# Logic_Engine_-_Front_LED.net
KiCad netlist of a schematic drawn in EAGLE
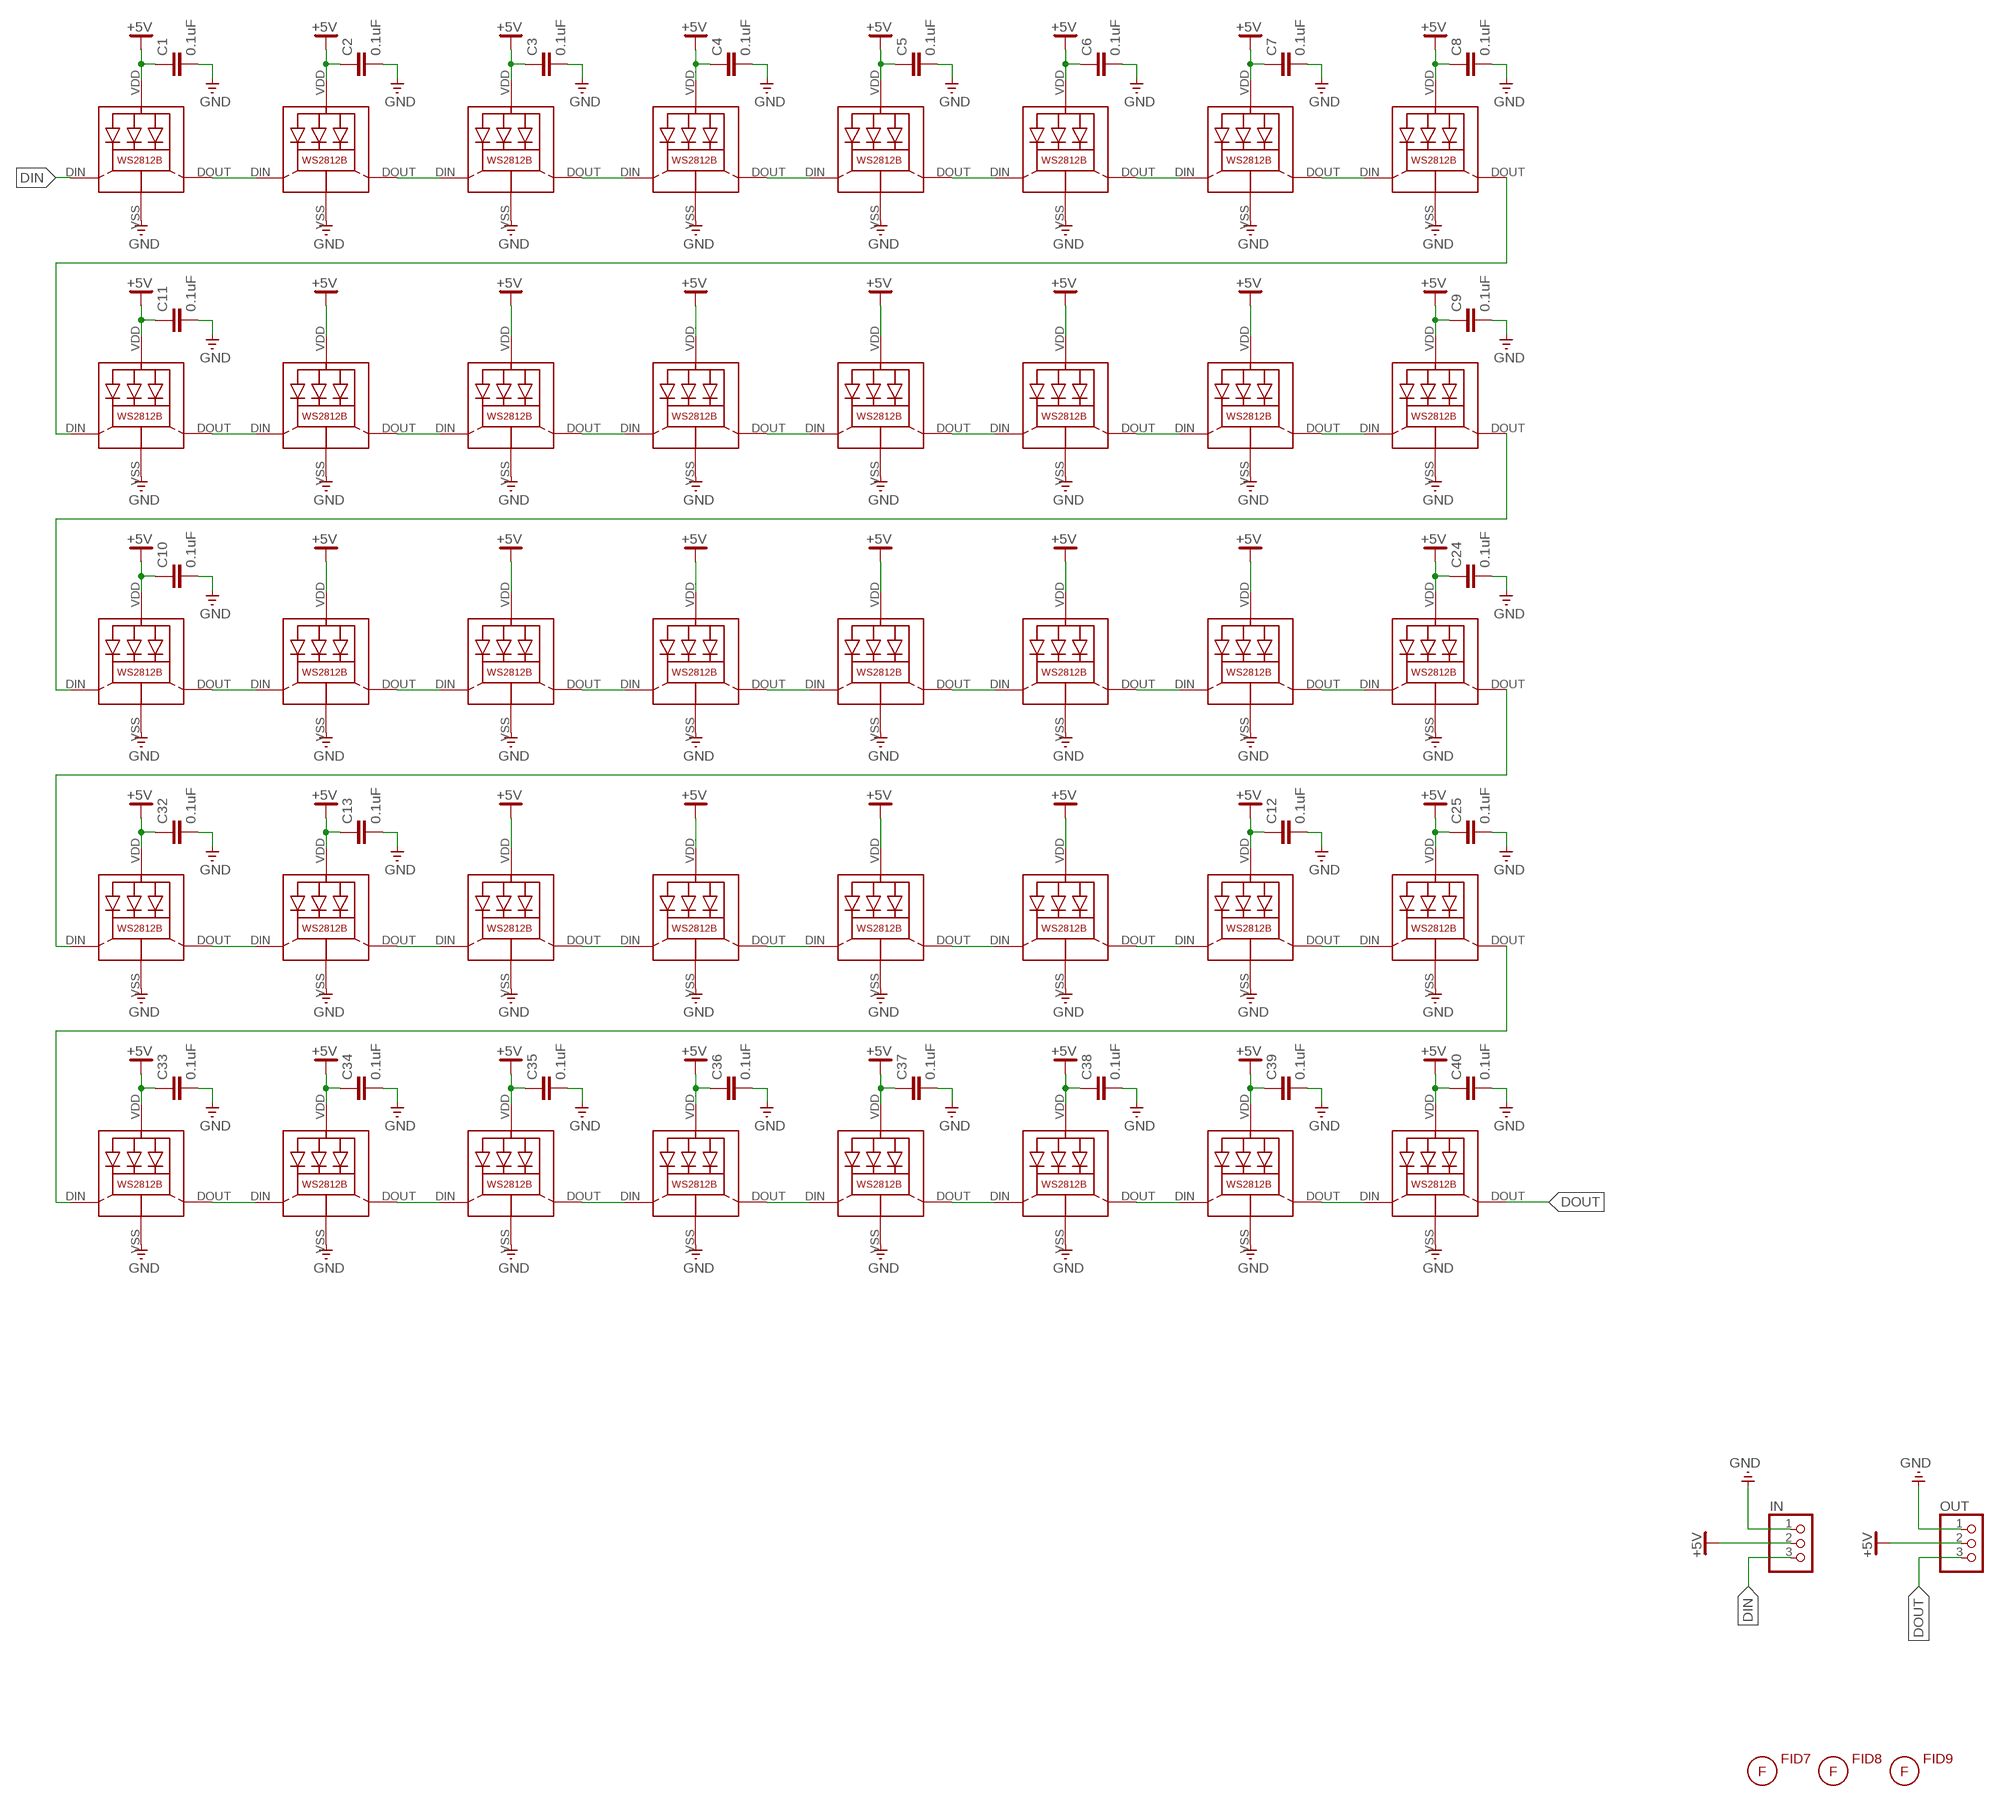
[diagram p0: schematic, sheet 1]

(export (version "E")
  (design (tool "Eeschema 10.0.6"))
  (components
    (comp (ref "C1")
      (value "0.1uF")
      (footprint "eagle-import:0603-CAP")
      (libsource (lib "eagle-import") (part "CAP0603-CAP"))
    )
    (comp (ref "C2")
      (value "0.1uF")
      (footprint "eagle-import:0603-CAP")
      (libsource (lib "eagle-import") (part "CAP0603-CAP"))
    )
    (comp (ref "C3")
      (value "0.1uF")
      (footprint "eagle-import:0603-CAP")
      (libsource (lib "eagle-import") (part "CAP0603-CAP"))
    )
    (comp (ref "C4")
      (value "0.1uF")
      (footprint "eagle-import:0603-CAP")
      (libsource (lib "eagle-import") (part "CAP0603-CAP"))
    )
    (comp (ref "C5")
      (value "0.1uF")
      (footprint "eagle-import:0603-CAP")
      (libsource (lib "eagle-import") (part "CAP0603-CAP"))
    )
    (comp (ref "C6")
      (value "0.1uF")
      (footprint "eagle-import:0603-CAP")
      (libsource (lib "eagle-import") (part "CAP0603-CAP"))
    )
    (comp (ref "C7")
      (value "0.1uF")
      (footprint "eagle-import:0603-CAP")
      (libsource (lib "eagle-import") (part "CAP0603-CAP"))
    )
    (comp (ref "C8")
      (value "0.1uF")
      (footprint "eagle-import:0603-CAP")
      (libsource (lib "eagle-import") (part "CAP0603-CAP"))
    )
    (comp (ref "C9")
      (value "0.1uF")
      (footprint "eagle-import:0603-CAP")
      (libsource (lib "eagle-import") (part "CAP0603-CAP"))
    )
    (comp (ref "C10")
      (value "0.1uF")
      (footprint "eagle-import:0603-CAP")
      (libsource (lib "eagle-import") (part "CAP0603-CAP"))
    )
    (comp (ref "C11")
      (value "0.1uF")
      (footprint "eagle-import:0603-CAP")
      (libsource (lib "eagle-import") (part "CAP0603-CAP"))
    )
    (comp (ref "C12")
      (value "0.1uF")
      (footprint "eagle-import:0603-CAP")
      (libsource (lib "eagle-import") (part "CAP0603-CAP"))
    )
    (comp (ref "C13")
      (value "0.1uF")
      (footprint "eagle-import:0603-CAP")
      (libsource (lib "eagle-import") (part "CAP0603-CAP"))
    )
    (comp (ref "C24")
      (value "0.1uF")
      (footprint "eagle-import:0603-CAP")
      (libsource (lib "eagle-import") (part "CAP0603-CAP"))
    )
    (comp (ref "C25")
      (value "0.1uF")
      (footprint "eagle-import:0603-CAP")
      (libsource (lib "eagle-import") (part "CAP0603-CAP"))
    )
    (comp (ref "C32")
      (value "0.1uF")
      (footprint "eagle-import:0603-CAP")
      (libsource (lib "eagle-import") (part "CAP0603-CAP"))
    )
    (comp (ref "C33")
      (value "0.1uF")
      (footprint "eagle-import:0603-CAP")
      (libsource (lib "eagle-import") (part "CAP0603-CAP"))
    )
    (comp (ref "C34")
      (value "0.1uF")
      (footprint "eagle-import:0603-CAP")
      (libsource (lib "eagle-import") (part "CAP0603-CAP"))
    )
    (comp (ref "C35")
      (value "0.1uF")
      (footprint "eagle-import:0603-CAP")
      (libsource (lib "eagle-import") (part "CAP0603-CAP"))
    )
    (comp (ref "C36")
      (value "0.1uF")
      (footprint "eagle-import:0603-CAP")
      (libsource (lib "eagle-import") (part "CAP0603-CAP"))
    )
    (comp (ref "C37")
      (value "0.1uF")
      (footprint "eagle-import:0603-CAP")
      (libsource (lib "eagle-import") (part "CAP0603-CAP"))
    )
    (comp (ref "C38")
      (value "0.1uF")
      (footprint "eagle-import:0603-CAP")
      (libsource (lib "eagle-import") (part "CAP0603-CAP"))
    )
    (comp (ref "C39")
      (value "0.1uF")
      (footprint "eagle-import:0603-CAP")
      (libsource (lib "eagle-import") (part "CAP0603-CAP"))
    )
    (comp (ref "C40")
      (value "0.1uF")
      (footprint "eagle-import:0603-CAP")
      (libsource (lib "eagle-import") (part "CAP0603-CAP"))
    )
    (comp (ref "FID7")
      (value "FIDUCIAL")
      (footprint "eagle-import:FIDUCIAL_G15")
      (libsource (lib "eagle-import") (part "FIDUCIAL"))
    )
    (comp (ref "FID8")
      (value "FIDUCIAL")
      (footprint "eagle-import:FIDUCIAL_G15")
      (libsource (lib "eagle-import") (part "FIDUCIAL"))
    )
    (comp (ref "FID9")
      (value "FIDUCIAL")
      (footprint "eagle-import:FIDUCIAL_G15")
      (libsource (lib "eagle-import") (part "FIDUCIAL"))
    )
    (comp (ref "IN")
      (value "PINHD-1X3")
      (footprint "eagle-import:1X03")
      (libsource (lib "eagle-import") (part "PINHD-1X3"))
    )
    (comp (ref "L1")
      (value "WS2812B")
      (footprint "eagle-import:WS2812B")
      (libsource (lib "eagle-import") (part "WS2812B"))
    )
    (comp (ref "L2")
      (value "WS2812B")
      (footprint "eagle-import:WS2812B")
      (libsource (lib "eagle-import") (part "WS2812B"))
    )
    (comp (ref "L3")
      (value "WS2812B")
      (footprint "eagle-import:WS2812B")
      (libsource (lib "eagle-import") (part "WS2812B"))
    )
    (comp (ref "L4")
      (value "WS2812B")
      (footprint "eagle-import:WS2812B")
      (libsource (lib "eagle-import") (part "WS2812B"))
    )
    (comp (ref "L5")
      (value "WS2812B")
      (footprint "eagle-import:WS2812B")
      (libsource (lib "eagle-import") (part "WS2812B"))
    )
    (comp (ref "L6")
      (value "WS2812B")
      (footprint "eagle-import:WS2812B")
      (libsource (lib "eagle-import") (part "WS2812B"))
    )
    (comp (ref "L7")
      (value "WS2812B")
      (footprint "eagle-import:WS2812B")
      (libsource (lib "eagle-import") (part "WS2812B"))
    )
    (comp (ref "L8")
      (value "WS2812B")
      (footprint "eagle-import:WS2812B")
      (libsource (lib "eagle-import") (part "WS2812B"))
    )
    (comp (ref "L9")
      (value "WS2812B")
      (footprint "eagle-import:WS2812B")
      (libsource (lib "eagle-import") (part "WS2812B"))
    )
    (comp (ref "L10")
      (value "WS2812B")
      (footprint "eagle-import:WS2812B")
      (libsource (lib "eagle-import") (part "WS2812B"))
    )
    (comp (ref "L11")
      (value "WS2812B")
      (footprint "eagle-import:WS2812B")
      (libsource (lib "eagle-import") (part "WS2812B"))
    )
    (comp (ref "L12")
      (value "WS2812B")
      (footprint "eagle-import:WS2812B")
      (libsource (lib "eagle-import") (part "WS2812B"))
    )
    (comp (ref "L13")
      (value "WS2812B")
      (footprint "eagle-import:WS2812B")
      (libsource (lib "eagle-import") (part "WS2812B"))
    )
    (comp (ref "L14")
      (value "WS2812B")
      (footprint "eagle-import:WS2812B")
      (libsource (lib "eagle-import") (part "WS2812B"))
    )
    (comp (ref "L15")
      (value "WS2812B")
      (footprint "eagle-import:WS2812B")
      (libsource (lib "eagle-import") (part "WS2812B"))
    )
    (comp (ref "L16")
      (value "WS2812B")
      (footprint "eagle-import:WS2812B")
      (libsource (lib "eagle-import") (part "WS2812B"))
    )
    (comp (ref "L17")
      (value "WS2812B")
      (footprint "eagle-import:WS2812B")
      (libsource (lib "eagle-import") (part "WS2812B"))
    )
    (comp (ref "L18")
      (value "WS2812B")
      (footprint "eagle-import:WS2812B")
      (libsource (lib "eagle-import") (part "WS2812B"))
    )
    (comp (ref "L19")
      (value "WS2812B")
      (footprint "eagle-import:WS2812B")
      (libsource (lib "eagle-import") (part "WS2812B"))
    )
    (comp (ref "L20")
      (value "WS2812B")
      (footprint "eagle-import:WS2812B")
      (libsource (lib "eagle-import") (part "WS2812B"))
    )
    (comp (ref "L21")
      (value "WS2812B")
      (footprint "eagle-import:WS2812B")
      (libsource (lib "eagle-import") (part "WS2812B"))
    )
    (comp (ref "L22")
      (value "WS2812B")
      (footprint "eagle-import:WS2812B")
      (libsource (lib "eagle-import") (part "WS2812B"))
    )
    (comp (ref "L23")
      (value "WS2812B")
      (footprint "eagle-import:WS2812B")
      (libsource (lib "eagle-import") (part "WS2812B"))
    )
    (comp (ref "L24")
      (value "WS2812B")
      (footprint "eagle-import:WS2812B")
      (libsource (lib "eagle-import") (part "WS2812B"))
    )
    (comp (ref "L25")
      (value "WS2812B")
      (footprint "eagle-import:WS2812B")
      (libsource (lib "eagle-import") (part "WS2812B"))
    )
    (comp (ref "L26")
      (value "WS2812B")
      (footprint "eagle-import:WS2812B")
      (libsource (lib "eagle-import") (part "WS2812B"))
    )
    (comp (ref "L27")
      (value "WS2812B")
      (footprint "eagle-import:WS2812B")
      (libsource (lib "eagle-import") (part "WS2812B"))
    )
    (comp (ref "L28")
      (value "WS2812B")
      (footprint "eagle-import:WS2812B")
      (libsource (lib "eagle-import") (part "WS2812B"))
    )
    (comp (ref "L29")
      (value "WS2812B")
      (footprint "eagle-import:WS2812B")
      (libsource (lib "eagle-import") (part "WS2812B"))
    )
    (comp (ref "L30")
      (value "WS2812B")
      (footprint "eagle-import:WS2812B")
      (libsource (lib "eagle-import") (part "WS2812B"))
    )
    (comp (ref "L31")
      (value "WS2812B")
      (footprint "eagle-import:WS2812B")
      (libsource (lib "eagle-import") (part "WS2812B"))
    )
    (comp (ref "L32")
      (value "WS2812B")
      (footprint "eagle-import:WS2812B")
      (libsource (lib "eagle-import") (part "WS2812B"))
    )
    (comp (ref "L33")
      (value "WS2812B")
      (footprint "eagle-import:WS2812B")
      (libsource (lib "eagle-import") (part "WS2812B"))
    )
    (comp (ref "L34")
      (value "WS2812B")
      (footprint "eagle-import:WS2812B")
      (libsource (lib "eagle-import") (part "WS2812B"))
    )
    (comp (ref "L35")
      (value "WS2812B")
      (footprint "eagle-import:WS2812B")
      (libsource (lib "eagle-import") (part "WS2812B"))
    )
    (comp (ref "L36")
      (value "WS2812B")
      (footprint "eagle-import:WS2812B")
      (libsource (lib "eagle-import") (part "WS2812B"))
    )
    (comp (ref "L37")
      (value "WS2812B")
      (footprint "eagle-import:WS2812B")
      (libsource (lib "eagle-import") (part "WS2812B"))
    )
    (comp (ref "L38")
      (value "WS2812B")
      (footprint "eagle-import:WS2812B")
      (libsource (lib "eagle-import") (part "WS2812B"))
    )
    (comp (ref "L39")
      (value "WS2812B")
      (footprint "eagle-import:WS2812B")
      (libsource (lib "eagle-import") (part "WS2812B"))
    )
    (comp (ref "L40")
      (value "WS2812B")
      (footprint "eagle-import:WS2812B")
      (libsource (lib "eagle-import") (part "WS2812B"))
    )
    (comp (ref "OUT")
      (value "PINHD-1X3")
      (footprint "eagle-import:1X03")
      (libsource (lib "eagle-import") (part "PINHD-1X3"))
    )
  )
  (nets
    (net (code "1") (name "+5V") (class "Default")
      (node (ref "C1") (pin "1") (pinfunction "1_1") (pintype "passive"))
      (node (ref "C10") (pin "1") (pinfunction "1_1") (pintype "passive"))
      (node (ref "C11") (pin "1") (pinfunction "1_1") (pintype "passive"))
      (node (ref "C12") (pin "1") (pinfunction "1_1") (pintype "passive"))
      (node (ref "C13") (pin "1") (pinfunction "1_1") (pintype "passive"))
      (node (ref "C2") (pin "1") (pinfunction "1_1") (pintype "passive"))
      (node (ref "C24") (pin "1") (pinfunction "1_1") (pintype "passive"))
      (node (ref "C25") (pin "1") (pinfunction "1_1") (pintype "passive"))
      (node (ref "C3") (pin "1") (pinfunction "1_1") (pintype "passive"))
      (node (ref "C32") (pin "1") (pinfunction "1_1") (pintype "passive"))
      (node (ref "C33") (pin "1") (pinfunction "1_1") (pintype "passive"))
      (node (ref "C34") (pin "1") (pinfunction "1_1") (pintype "passive"))
      (node (ref "C35") (pin "1") (pinfunction "1_1") (pintype "passive"))
      (node (ref "C36") (pin "1") (pinfunction "1_1") (pintype "passive"))
      (node (ref "C37") (pin "1") (pinfunction "1_1") (pintype "passive"))
      (node (ref "C38") (pin "1") (pinfunction "1_1") (pintype "passive"))
      (node (ref "C39") (pin "1") (pinfunction "1_1") (pintype "passive"))
      (node (ref "C4") (pin "1") (pinfunction "1_1") (pintype "passive"))
      (node (ref "C40") (pin "1") (pinfunction "1_1") (pintype "passive"))
      (node (ref "C5") (pin "1") (pinfunction "1_1") (pintype "passive"))
      (node (ref "C6") (pin "1") (pinfunction "1_1") (pintype "passive"))
      (node (ref "C7") (pin "1") (pinfunction "1_1") (pintype "passive"))
      (node (ref "C8") (pin "1") (pinfunction "1_1") (pintype "passive"))
      (node (ref "C9") (pin "1") (pinfunction "1_1") (pintype "passive"))
      (node (ref "IN") (pin "2") (pinfunction "2_2") (pintype "passive"))
      (node (ref "L1") (pin "VDD") (pinfunction "VDD_VDD") (pintype "power_in"))
      (node (ref "L10") (pin "VDD") (pinfunction "VDD_VDD") (pintype "power_in"))
      (node (ref "L11") (pin "VDD") (pinfunction "VDD_VDD") (pintype "power_in"))
      (node (ref "L12") (pin "VDD") (pinfunction "VDD_VDD") (pintype "power_in"))
      (node (ref "L13") (pin "VDD") (pinfunction "VDD_VDD") (pintype "power_in"))
      (node (ref "L14") (pin "VDD") (pinfunction "VDD_VDD") (pintype "power_in"))
      (node (ref "L15") (pin "VDD") (pinfunction "VDD_VDD") (pintype "power_in"))
      (node (ref "L16") (pin "VDD") (pinfunction "VDD_VDD") (pintype "power_in"))
      (node (ref "L17") (pin "VDD") (pinfunction "VDD_VDD") (pintype "power_in"))
      (node (ref "L18") (pin "VDD") (pinfunction "VDD_VDD") (pintype "power_in"))
      (node (ref "L19") (pin "VDD") (pinfunction "VDD_VDD") (pintype "power_in"))
      (node (ref "L2") (pin "VDD") (pinfunction "VDD_VDD") (pintype "power_in"))
      (node (ref "L20") (pin "VDD") (pinfunction "VDD_VDD") (pintype "power_in"))
      (node (ref "L21") (pin "VDD") (pinfunction "VDD_VDD") (pintype "power_in"))
      (node (ref "L22") (pin "VDD") (pinfunction "VDD_VDD") (pintype "power_in"))
      (node (ref "L23") (pin "VDD") (pinfunction "VDD_VDD") (pintype "power_in"))
      (node (ref "L24") (pin "VDD") (pinfunction "VDD_VDD") (pintype "power_in"))
      (node (ref "L25") (pin "VDD") (pinfunction "VDD_VDD") (pintype "power_in"))
      (node (ref "L26") (pin "VDD") (pinfunction "VDD_VDD") (pintype "power_in"))
      (node (ref "L27") (pin "VDD") (pinfunction "VDD_VDD") (pintype "power_in"))
      (node (ref "L28") (pin "VDD") (pinfunction "VDD_VDD") (pintype "power_in"))
      (node (ref "L29") (pin "VDD") (pinfunction "VDD_VDD") (pintype "power_in"))
      (node (ref "L3") (pin "VDD") (pinfunction "VDD_VDD") (pintype "power_in"))
      (node (ref "L30") (pin "VDD") (pinfunction "VDD_VDD") (pintype "power_in"))
      (node (ref "L31") (pin "VDD") (pinfunction "VDD_VDD") (pintype "power_in"))
      (node (ref "L32") (pin "VDD") (pinfunction "VDD_VDD") (pintype "power_in"))
      (node (ref "L33") (pin "VDD") (pinfunction "VDD_VDD") (pintype "power_in"))
      (node (ref "L34") (pin "VDD") (pinfunction "VDD_VDD") (pintype "power_in"))
      (node (ref "L35") (pin "VDD") (pinfunction "VDD_VDD") (pintype "power_in"))
      (node (ref "L36") (pin "VDD") (pinfunction "VDD_VDD") (pintype "power_in"))
      (node (ref "L37") (pin "VDD") (pinfunction "VDD_VDD") (pintype "power_in"))
      (node (ref "L38") (pin "VDD") (pinfunction "VDD_VDD") (pintype "power_in"))
      (node (ref "L39") (pin "VDD") (pinfunction "VDD_VDD") (pintype "power_in"))
      (node (ref "L4") (pin "VDD") (pinfunction "VDD_VDD") (pintype "power_in"))
      (node (ref "L40") (pin "VDD") (pinfunction "VDD_VDD") (pintype "power_in"))
      (node (ref "L5") (pin "VDD") (pinfunction "VDD_VDD") (pintype "power_in"))
      (node (ref "L6") (pin "VDD") (pinfunction "VDD_VDD") (pintype "power_in"))
      (node (ref "L7") (pin "VDD") (pinfunction "VDD_VDD") (pintype "power_in"))
      (node (ref "L8") (pin "VDD") (pinfunction "VDD_VDD") (pintype "power_in"))
      (node (ref "L9") (pin "VDD") (pinfunction "VDD_VDD") (pintype "power_in"))
      (node (ref "OUT") (pin "2") (pinfunction "2_2") (pintype "passive"))
    )
    (net (code "2") (name "DIN") (class "Default")
      (node (ref "IN") (pin "3") (pinfunction "3_3") (pintype "passive"))
      (node (ref "L1") (pin "DIN") (pinfunction "DI_DIN") (pintype "input"))
    )
    (net (code "3") (name "DOUT") (class "Default")
      (node (ref "L40") (pin "DOUT") (pinfunction "DO_DOUT") (pintype "output"))
      (node (ref "OUT") (pin "3") (pinfunction "3_3") (pintype "passive"))
    )
    (net (code "4") (name "GND") (class "Default")
      (node (ref "C1") (pin "2") (pinfunction "2_2") (pintype "passive"))
      (node (ref "C10") (pin "2") (pinfunction "2_2") (pintype "passive"))
      (node (ref "C11") (pin "2") (pinfunction "2_2") (pintype "passive"))
      (node (ref "C12") (pin "2") (pinfunction "2_2") (pintype "passive"))
      (node (ref "C13") (pin "2") (pinfunction "2_2") (pintype "passive"))
      (node (ref "C2") (pin "2") (pinfunction "2_2") (pintype "passive"))
      (node (ref "C24") (pin "2") (pinfunction "2_2") (pintype "passive"))
      (node (ref "C25") (pin "2") (pinfunction "2_2") (pintype "passive"))
      (node (ref "C3") (pin "2") (pinfunction "2_2") (pintype "passive"))
      (node (ref "C32") (pin "2") (pinfunction "2_2") (pintype "passive"))
      (node (ref "C33") (pin "2") (pinfunction "2_2") (pintype "passive"))
      (node (ref "C34") (pin "2") (pinfunction "2_2") (pintype "passive"))
      (node (ref "C35") (pin "2") (pinfunction "2_2") (pintype "passive"))
      (node (ref "C36") (pin "2") (pinfunction "2_2") (pintype "passive"))
      (node (ref "C37") (pin "2") (pinfunction "2_2") (pintype "passive"))
      (node (ref "C38") (pin "2") (pinfunction "2_2") (pintype "passive"))
      (node (ref "C39") (pin "2") (pinfunction "2_2") (pintype "passive"))
      (node (ref "C4") (pin "2") (pinfunction "2_2") (pintype "passive"))
      (node (ref "C40") (pin "2") (pinfunction "2_2") (pintype "passive"))
      (node (ref "C5") (pin "2") (pinfunction "2_2") (pintype "passive"))
      (node (ref "C6") (pin "2") (pinfunction "2_2") (pintype "passive"))
      (node (ref "C7") (pin "2") (pinfunction "2_2") (pintype "passive"))
      (node (ref "C8") (pin "2") (pinfunction "2_2") (pintype "passive"))
      (node (ref "C9") (pin "2") (pinfunction "2_2") (pintype "passive"))
      (node (ref "IN") (pin "1") (pinfunction "1_1") (pintype "passive"))
      (node (ref "L1") (pin "VSS") (pinfunction "GND_VSS") (pintype "power_in"))
      (node (ref "L10") (pin "VSS") (pinfunction "GND_VSS") (pintype "power_in"))
      (node (ref "L11") (pin "VSS") (pinfunction "GND_VSS") (pintype "power_in"))
      (node (ref "L12") (pin "VSS") (pinfunction "GND_VSS") (pintype "power_in"))
      (node (ref "L13") (pin "VSS") (pinfunction "GND_VSS") (pintype "power_in"))
      (node (ref "L14") (pin "VSS") (pinfunction "GND_VSS") (pintype "power_in"))
      (node (ref "L15") (pin "VSS") (pinfunction "GND_VSS") (pintype "power_in"))
      (node (ref "L16") (pin "VSS") (pinfunction "GND_VSS") (pintype "power_in"))
      (node (ref "L17") (pin "VSS") (pinfunction "GND_VSS") (pintype "power_in"))
      (node (ref "L18") (pin "VSS") (pinfunction "GND_VSS") (pintype "power_in"))
      (node (ref "L19") (pin "VSS") (pinfunction "GND_VSS") (pintype "power_in"))
      (node (ref "L2") (pin "VSS") (pinfunction "GND_VSS") (pintype "power_in"))
      (node (ref "L20") (pin "VSS") (pinfunction "GND_VSS") (pintype "power_in"))
      (node (ref "L21") (pin "VSS") (pinfunction "GND_VSS") (pintype "power_in"))
      (node (ref "L22") (pin "VSS") (pinfunction "GND_VSS") (pintype "power_in"))
      (node (ref "L23") (pin "VSS") (pinfunction "GND_VSS") (pintype "power_in"))
      (node (ref "L24") (pin "VSS") (pinfunction "GND_VSS") (pintype "power_in"))
      (node (ref "L25") (pin "VSS") (pinfunction "GND_VSS") (pintype "power_in"))
      (node (ref "L26") (pin "VSS") (pinfunction "GND_VSS") (pintype "power_in"))
      (node (ref "L27") (pin "VSS") (pinfunction "GND_VSS") (pintype "power_in"))
      (node (ref "L28") (pin "VSS") (pinfunction "GND_VSS") (pintype "power_in"))
      (node (ref "L29") (pin "VSS") (pinfunction "GND_VSS") (pintype "power_in"))
      (node (ref "L3") (pin "VSS") (pinfunction "GND_VSS") (pintype "power_in"))
      (node (ref "L30") (pin "VSS") (pinfunction "GND_VSS") (pintype "power_in"))
      (node (ref "L31") (pin "VSS") (pinfunction "GND_VSS") (pintype "power_in"))
      (node (ref "L32") (pin "VSS") (pinfunction "GND_VSS") (pintype "power_in"))
      (node (ref "L33") (pin "VSS") (pinfunction "GND_VSS") (pintype "power_in"))
      (node (ref "L34") (pin "VSS") (pinfunction "GND_VSS") (pintype "power_in"))
      (node (ref "L35") (pin "VSS") (pinfunction "GND_VSS") (pintype "power_in"))
      (node (ref "L36") (pin "VSS") (pinfunction "GND_VSS") (pintype "power_in"))
      (node (ref "L37") (pin "VSS") (pinfunction "GND_VSS") (pintype "power_in"))
      (node (ref "L38") (pin "VSS") (pinfunction "GND_VSS") (pintype "power_in"))
      (node (ref "L39") (pin "VSS") (pinfunction "GND_VSS") (pintype "power_in"))
      (node (ref "L4") (pin "VSS") (pinfunction "GND_VSS") (pintype "power_in"))
      (node (ref "L40") (pin "VSS") (pinfunction "GND_VSS") (pintype "power_in"))
      (node (ref "L5") (pin "VSS") (pinfunction "GND_VSS") (pintype "power_in"))
      (node (ref "L6") (pin "VSS") (pinfunction "GND_VSS") (pintype "power_in"))
      (node (ref "L7") (pin "VSS") (pinfunction "GND_VSS") (pintype "power_in"))
      (node (ref "L8") (pin "VSS") (pinfunction "GND_VSS") (pintype "power_in"))
      (node (ref "L9") (pin "VSS") (pinfunction "GND_VSS") (pintype "power_in"))
      (node (ref "OUT") (pin "1") (pinfunction "1_1") (pintype "passive"))
    )
    (net (code "5") (name "Net-(L1-DO)") (class "Default")
      (node (ref "L1") (pin "DOUT") (pinfunction "DO_DOUT") (pintype "output"))
      (node (ref "L2") (pin "DIN") (pinfunction "DI_DIN") (pintype "input"))
    )
    (net (code "6") (name "Net-(L2-DO)") (class "Default")
      (node (ref "L2") (pin "DOUT") (pinfunction "DO_DOUT") (pintype "output"))
      (node (ref "L3") (pin "DIN") (pinfunction "DI_DIN") (pintype "input"))
    )
    (net (code "7") (name "Net-(L3-DO)") (class "Default")
      (node (ref "L3") (pin "DOUT") (pinfunction "DO_DOUT") (pintype "output"))
      (node (ref "L4") (pin "DIN") (pinfunction "DI_DIN") (pintype "input"))
    )
    (net (code "8") (name "Net-(L4-DO)") (class "Default")
      (node (ref "L4") (pin "DOUT") (pinfunction "DO_DOUT") (pintype "output"))
      (node (ref "L5") (pin "DIN") (pinfunction "DI_DIN") (pintype "input"))
    )
    (net (code "9") (name "Net-(L5-DO)") (class "Default")
      (node (ref "L5") (pin "DOUT") (pinfunction "DO_DOUT") (pintype "output"))
      (node (ref "L6") (pin "DIN") (pinfunction "DI_DIN") (pintype "input"))
    )
    (net (code "10") (name "Net-(L6-DO)") (class "Default")
      (node (ref "L6") (pin "DOUT") (pinfunction "DO_DOUT") (pintype "output"))
      (node (ref "L7") (pin "DIN") (pinfunction "DI_DIN") (pintype "input"))
    )
    (net (code "11") (name "Net-(L7-DO)") (class "Default")
      (node (ref "L7") (pin "DOUT") (pinfunction "DO_DOUT") (pintype "output"))
      (node (ref "L8") (pin "DIN") (pinfunction "DI_DIN") (pintype "input"))
    )
    (net (code "12") (name "Net-(L8-DO)") (class "Default")
      (node (ref "L8") (pin "DOUT") (pinfunction "DO_DOUT") (pintype "output"))
      (node (ref "L9") (pin "DIN") (pinfunction "DI_DIN") (pintype "input"))
    )
    (net (code "13") (name "Net-(L10-DI)") (class "Default")
      (node (ref "L10") (pin "DIN") (pinfunction "DI_DIN") (pintype "input"))
      (node (ref "L9") (pin "DOUT") (pinfunction "DO_DOUT") (pintype "output"))
    )
    (net (code "14") (name "Net-(L10-DO)") (class "Default")
      (node (ref "L10") (pin "DOUT") (pinfunction "DO_DOUT") (pintype "output"))
      (node (ref "L11") (pin "DIN") (pinfunction "DI_DIN") (pintype "input"))
    )
    (net (code "15") (name "Net-(L11-DO)") (class "Default")
      (node (ref "L11") (pin "DOUT") (pinfunction "DO_DOUT") (pintype "output"))
      (node (ref "L12") (pin "DIN") (pinfunction "DI_DIN") (pintype "input"))
    )
    (net (code "16") (name "Net-(L12-DO)") (class "Default")
      (node (ref "L12") (pin "DOUT") (pinfunction "DO_DOUT") (pintype "output"))
      (node (ref "L13") (pin "DIN") (pinfunction "DI_DIN") (pintype "input"))
    )
    (net (code "17") (name "Net-(L13-DO)") (class "Default")
      (node (ref "L13") (pin "DOUT") (pinfunction "DO_DOUT") (pintype "output"))
      (node (ref "L14") (pin "DIN") (pinfunction "DI_DIN") (pintype "input"))
    )
    (net (code "18") (name "Net-(L14-DO)") (class "Default")
      (node (ref "L14") (pin "DOUT") (pinfunction "DO_DOUT") (pintype "output"))
      (node (ref "L15") (pin "DIN") (pinfunction "DI_DIN") (pintype "input"))
    )
    (net (code "19") (name "Net-(L15-DO)") (class "Default")
      (node (ref "L15") (pin "DOUT") (pinfunction "DO_DOUT") (pintype "output"))
      (node (ref "L16") (pin "DIN") (pinfunction "DI_DIN") (pintype "input"))
    )
    (net (code "20") (name "Net-(L16-DO)") (class "Default")
      (node (ref "L16") (pin "DOUT") (pinfunction "DO_DOUT") (pintype "output"))
      (node (ref "L17") (pin "DIN") (pinfunction "DI_DIN") (pintype "input"))
    )
    (net (code "21") (name "Net-(L17-DO)") (class "Default")
      (node (ref "L17") (pin "DOUT") (pinfunction "DO_DOUT") (pintype "output"))
      (node (ref "L18") (pin "DIN") (pinfunction "DI_DIN") (pintype "input"))
    )
    (net (code "22") (name "Net-(L18-DO)") (class "Default")
      (node (ref "L18") (pin "DOUT") (pinfunction "DO_DOUT") (pintype "output"))
      (node (ref "L19") (pin "DIN") (pinfunction "DI_DIN") (pintype "input"))
    )
    (net (code "23") (name "Net-(L19-DO)") (class "Default")
      (node (ref "L19") (pin "DOUT") (pinfunction "DO_DOUT") (pintype "output"))
      (node (ref "L20") (pin "DIN") (pinfunction "DI_DIN") (pintype "input"))
    )
    (net (code "24") (name "Net-(L20-DO)") (class "Default")
      (node (ref "L20") (pin "DOUT") (pinfunction "DO_DOUT") (pintype "output"))
      (node (ref "L21") (pin "DIN") (pinfunction "DI_DIN") (pintype "input"))
    )
    (net (code "25") (name "Net-(L21-DO)") (class "Default")
      (node (ref "L21") (pin "DOUT") (pinfunction "DO_DOUT") (pintype "output"))
      (node (ref "L22") (pin "DIN") (pinfunction "DI_DIN") (pintype "input"))
    )
    (net (code "26") (name "Net-(L22-DO)") (class "Default")
      (node (ref "L22") (pin "DOUT") (pinfunction "DO_DOUT") (pintype "output"))
      (node (ref "L23") (pin "DIN") (pinfunction "DI_DIN") (pintype "input"))
    )
    (net (code "27") (name "Net-(L23-DO)") (class "Default")
      (node (ref "L23") (pin "DOUT") (pinfunction "DO_DOUT") (pintype "output"))
      (node (ref "L24") (pin "DIN") (pinfunction "DI_DIN") (pintype "input"))
    )
    (net (code "28") (name "Net-(L24-DO)") (class "Default")
      (node (ref "L24") (pin "DOUT") (pinfunction "DO_DOUT") (pintype "output"))
      (node (ref "L25") (pin "DIN") (pinfunction "DI_DIN") (pintype "input"))
    )
    (net (code "29") (name "Net-(L25-DO)") (class "Default")
      (node (ref "L25") (pin "DOUT") (pinfunction "DO_DOUT") (pintype "output"))
      (node (ref "L26") (pin "DIN") (pinfunction "DI_DIN") (pintype "input"))
    )
    (net (code "30") (name "Net-(L26-DO)") (class "Default")
      (node (ref "L26") (pin "DOUT") (pinfunction "DO_DOUT") (pintype "output"))
      (node (ref "L27") (pin "DIN") (pinfunction "DI_DIN") (pintype "input"))
    )
    (net (code "31") (name "Net-(L27-DO)") (class "Default")
      (node (ref "L27") (pin "DOUT") (pinfunction "DO_DOUT") (pintype "output"))
      (node (ref "L28") (pin "DIN") (pinfunction "DI_DIN") (pintype "input"))
    )
    (net (code "32") (name "Net-(L28-DO)") (class "Default")
      (node (ref "L28") (pin "DOUT") (pinfunction "DO_DOUT") (pintype "output"))
      (node (ref "L29") (pin "DIN") (pinfunction "DI_DIN") (pintype "input"))
    )
    (net (code "33") (name "Net-(L29-DO)") (class "Default")
      (node (ref "L29") (pin "DOUT") (pinfunction "DO_DOUT") (pintype "output"))
      (node (ref "L30") (pin "DIN") (pinfunction "DI_DIN") (pintype "input"))
    )
    (net (code "34") (name "Net-(L30-DO)") (class "Default")
      (node (ref "L30") (pin "DOUT") (pinfunction "DO_DOUT") (pintype "output"))
      (node (ref "L31") (pin "DIN") (pinfunction "DI_DIN") (pintype "input"))
    )
    (net (code "35") (name "Net-(L31-DO)") (class "Default")
      (node (ref "L31") (pin "DOUT") (pinfunction "DO_DOUT") (pintype "output"))
      (node (ref "L32") (pin "DIN") (pinfunction "DI_DIN") (pintype "input"))
    )
    (net (code "36") (name "Net-(L32-DO)") (class "Default")
      (node (ref "L32") (pin "DOUT") (pinfunction "DO_DOUT") (pintype "output"))
      (node (ref "L33") (pin "DIN") (pinfunction "DI_DIN") (pintype "input"))
    )
    (net (code "37") (name "Net-(L33-DO)") (class "Default")
      (node (ref "L33") (pin "DOUT") (pinfunction "DO_DOUT") (pintype "output"))
      (node (ref "L34") (pin "DIN") (pinfunction "DI_DIN") (pintype "input"))
    )
    (net (code "38") (name "Net-(L34-DO)") (class "Default")
      (node (ref "L34") (pin "DOUT") (pinfunction "DO_DOUT") (pintype "output"))
      (node (ref "L35") (pin "DIN") (pinfunction "DI_DIN") (pintype "input"))
    )
    (net (code "39") (name "Net-(L35-DO)") (class "Default")
      (node (ref "L35") (pin "DOUT") (pinfunction "DO_DOUT") (pintype "output"))
      (node (ref "L36") (pin "DIN") (pinfunction "DI_DIN") (pintype "input"))
    )
    (net (code "40") (name "Net-(L36-DO)") (class "Default")
      (node (ref "L36") (pin "DOUT") (pinfunction "DO_DOUT") (pintype "output"))
      (node (ref "L37") (pin "DIN") (pinfunction "DI_DIN") (pintype "input"))
    )
    (net (code "41") (name "Net-(L37-DO)") (class "Default")
      (node (ref "L37") (pin "DOUT") (pinfunction "DO_DOUT") (pintype "output"))
      (node (ref "L38") (pin "DIN") (pinfunction "DI_DIN") (pintype "input"))
    )
    (net (code "42") (name "Net-(L38-DO)") (class "Default")
      (node (ref "L38") (pin "DOUT") (pinfunction "DO_DOUT") (pintype "output"))
      (node (ref "L39") (pin "DIN") (pinfunction "DI_DIN") (pintype "input"))
    )
    (net (code "43") (name "Net-(L39-DO)") (class "Default")
      (node (ref "L39") (pin "DOUT") (pinfunction "DO_DOUT") (pintype "output"))
      (node (ref "L40") (pin "DIN") (pinfunction "DI_DIN") (pintype "input"))
    )
  )
)
